# Wemos_P1_DSMR5_hat.net
KiCad netlist of a schematic drawn in EasyEDA
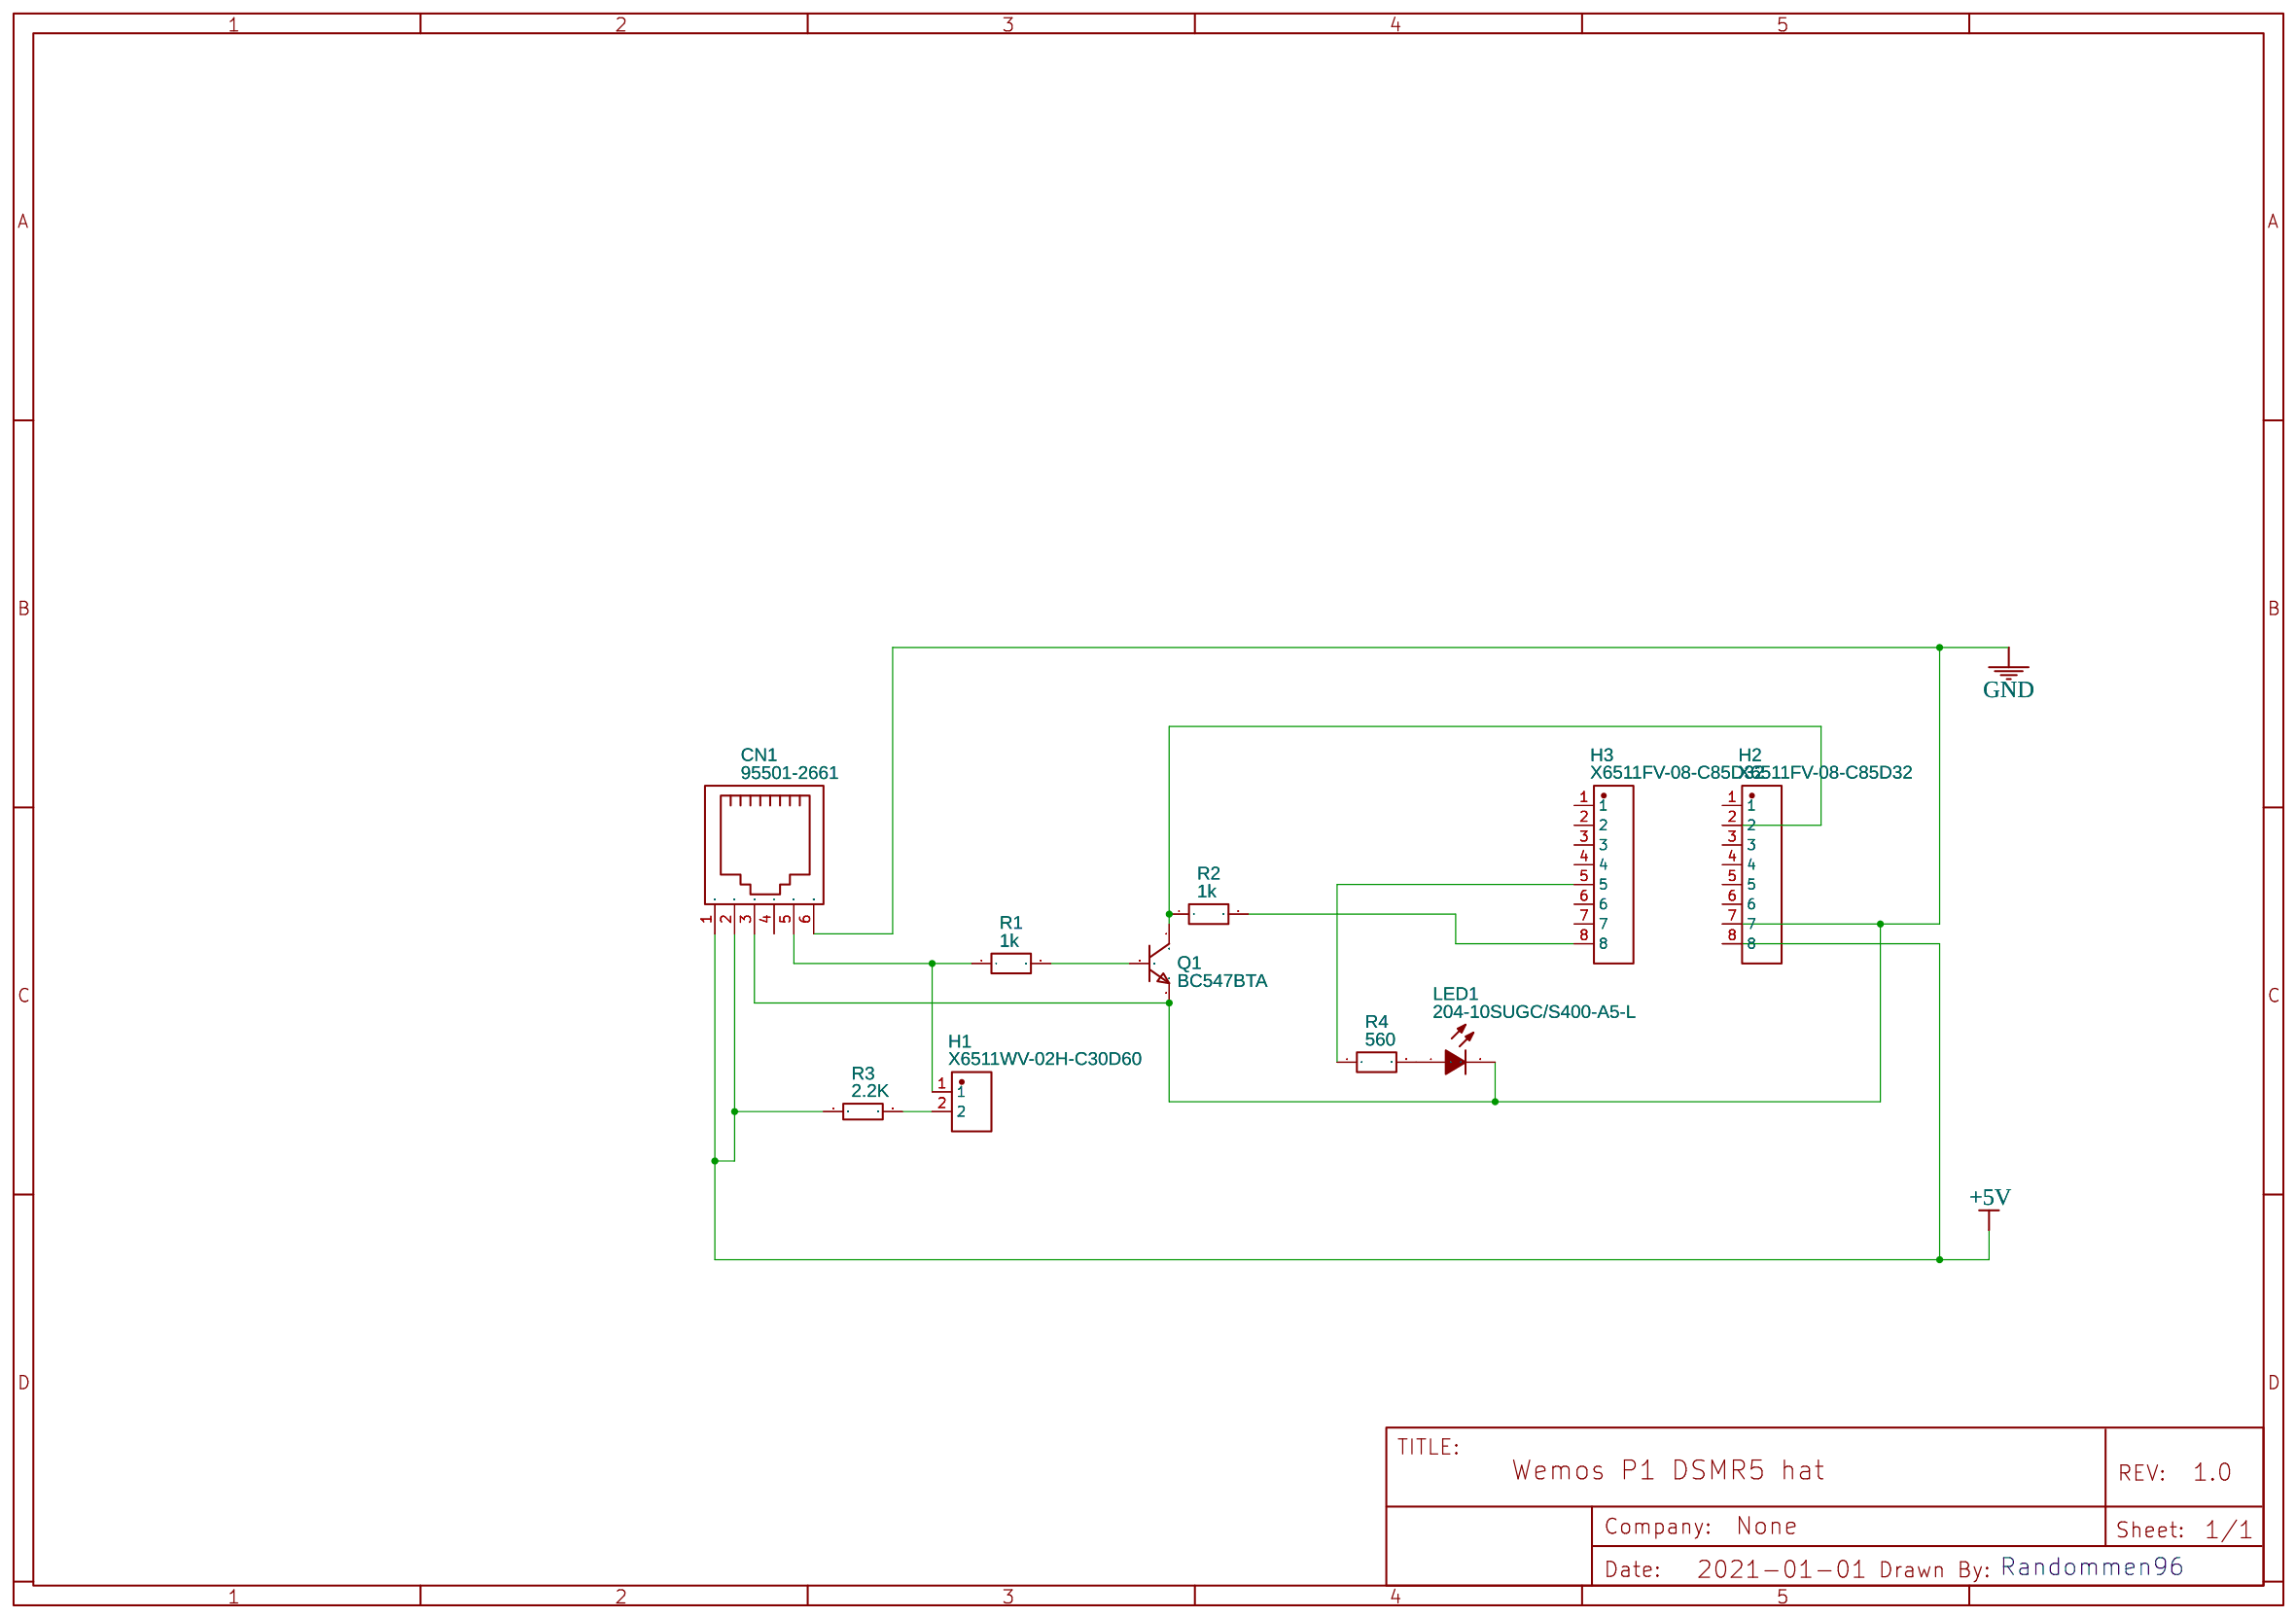
[diagram p0: schematic sheet]

(export (version "E")
  (design (tool "Eeschema 10.0.6"))
  (components
    (comp (ref "CN1")
      (value "95501-2661")
      (fields (field (name "BOM_Supplier Part") "C240856"))
      (libsource (lib "") (part "95501-2661"))
    )
    (comp (ref "H1")
      (value "X6511WV-02H-C30D60")
      (fields (field (name "BOM_Supplier Part") "C706874"))
      (libsource (lib "") (part "X6511WV-02H-C30D60"))
    )
    (comp (ref "H2")
      (value "X6511FV-08-C85D32")
      (fields (field (name "BOM_Supplier Part") "C718237"))
      (libsource (lib "") (part "X6511FV-08-C85D32"))
    )
    (comp (ref "H3")
      (value "X6511FV-08-C85D32")
      (fields (field (name "BOM_Supplier Part") "C718237"))
      (libsource (lib "") (part "X6511FV-08-C85D32"))
    )
    (comp (ref "LED1")
      (value "204-10SUGC/S400-A5-L")
      (fields (field (name "BOM_Supplier Part") "C99763"))
      (libsource (lib "") (part "204-10SUGC/S400-A5-L"))
    )
    (comp (ref "Q1")
      (value "BC547BTA")
      (fields (field (name "BOM_Supplier Part") "C258144"))
      (libsource (lib "") (part "BC547BTA"))
    )
    (comp (ref "R1")
      (value "1k")
      (fields
        (field (name "BOM_Manufacturer Part") "CFR0W4J0102A50")
        (field (name "BOM_Supplier Part") "C66649")
      )
      (libsource (lib "") (part "CFR0W4J0102A50_C66649"))
    )
    (comp (ref "R2")
      (value "1k")
      (fields
        (field (name "BOM_Manufacturer Part") "CFR0W4J0102A50")
        (field (name "BOM_Supplier Part") "C66649")
      )
      (libsource (lib "") (part "CFR0W4J0102A50_C66649"))
    )
    (comp (ref "R3")
      (value "2.2K")
      (fields
        (field (name "BOM_Manufacturer Part") "CFR0W4J0222A50")
        (field (name "BOM_Supplier Part") "C61295")
      )
      (libsource (lib "") (part "CFR0W4J0222A50"))
    )
    (comp (ref "R4")
      (value "560")
      (fields
        (field (name "BOM_Manufacturer Part") "RD 1/4W 560R J T/B A1")
        (field (name "BOM_Supplier Part") "C433706")
      )
      (libsource (lib "") (part "RD 1/4W 560R J T/B A1"))
    )
  )
  (nets
    (net (code "1") (name "+5V") (class "Default")
      (node (ref "CN1") (pin "1") (pinfunction "1_1") (pintype "unspecified"))
      (node (ref "CN1") (pin "2") (pinfunction "2_2") (pintype "unspecified"))
      (node (ref "H2") (pin "8") (pinfunction "8_8") (pintype "unspecified"))
      (node (ref "R3") (pin "1") (pinfunction "1_1") (pintype "input"))
    )
    (net (code "2") (name "GND") (class "Default")
      (node (ref "CN1") (pin "3") (pinfunction "3_3") (pintype "unspecified"))
      (node (ref "CN1") (pin "6") (pinfunction "6_6") (pintype "unspecified"))
      (node (ref "H2") (pin "7") (pinfunction "7_7") (pintype "unspecified"))
      (node (ref "LED1") (pin "2") (pinfunction "K_2") (pintype "input"))
      (node (ref "Q1") (pin "3") (pinfunction "E_3") (pintype "unspecified"))
    )
    (net (code "3") (name "Net-(CN1-Pad5)") (class "Default")
      (node (ref "CN1") (pin "5") (pinfunction "5_5") (pintype "unspecified"))
      (node (ref "H1") (pin "1") (pinfunction "1_1") (pintype "unspecified"))
      (node (ref "R1") (pin "1") (pinfunction "1_1") (pintype "unspecified"))
    )
    (net (code "4") (name "Net-(H1-Pad2)") (class "Default")
      (node (ref "H1") (pin "2") (pinfunction "2_2") (pintype "unspecified"))
      (node (ref "R3") (pin "2") (pinfunction "2_2") (pintype "input"))
    )
    (net (code "5") (name "Net-(H3-Pad5)") (class "Default")
      (node (ref "H3") (pin "5") (pinfunction "5_5") (pintype "unspecified"))
      (node (ref "R4") (pin "1") (pinfunction "1_1") (pintype "unspecified"))
    )
    (net (code "6") (name "Net-(H3-Pad8)") (class "Default")
      (node (ref "H3") (pin "8") (pinfunction "8_8") (pintype "unspecified"))
      (node (ref "R2") (pin "2") (pinfunction "2_2") (pintype "unspecified"))
    )
    (net (code "7") (name "Net-(LED1-A)") (class "Default")
      (node (ref "LED1") (pin "1") (pinfunction "A_1") (pintype "input"))
      (node (ref "R4") (pin "2") (pinfunction "2_2") (pintype "unspecified"))
    )
    (net (code "8") (name "Net-(Q1-B)") (class "Default")
      (node (ref "Q1") (pin "2") (pinfunction "B_2") (pintype "unspecified"))
      (node (ref "R1") (pin "2") (pinfunction "2_2") (pintype "unspecified"))
    )
    (net (code "9") (name "Net-(Q1-C)") (class "Default")
      (node (ref "H2") (pin "2") (pinfunction "2_2") (pintype "unspecified"))
      (node (ref "Q1") (pin "1") (pinfunction "C_1") (pintype "unspecified"))
      (node (ref "R2") (pin "1") (pinfunction "1_1") (pintype "unspecified"))
    )
    (net (code "10") (name "unconnected-(CN1-Pad4)") (class "Default")
      (node (ref "CN1") (pin "4") (pinfunction "4_4") (pintype "unspecified"))
    )
    (net (code "11") (name "unconnected-(H2-Pad1)") (class "Default")
      (node (ref "H2") (pin "1") (pinfunction "1_1") (pintype "unspecified"))
    )
    (net (code "12") (name "unconnected-(H2-Pad3)") (class "Default")
      (node (ref "H2") (pin "3") (pinfunction "3_3") (pintype "unspecified"))
    )
    (net (code "13") (name "unconnected-(H2-Pad4)") (class "Default")
      (node (ref "H2") (pin "4") (pinfunction "4_4") (pintype "unspecified"))
    )
    (net (code "14") (name "unconnected-(H2-Pad5)") (class "Default")
      (node (ref "H2") (pin "5") (pinfunction "5_5") (pintype "unspecified"))
    )
    (net (code "15") (name "unconnected-(H2-Pad6)") (class "Default")
      (node (ref "H2") (pin "6") (pinfunction "6_6") (pintype "unspecified"))
    )
    (net (code "16") (name "unconnected-(H3-Pad1)") (class "Default")
      (node (ref "H3") (pin "1") (pinfunction "1_1") (pintype "unspecified"))
    )
    (net (code "17") (name "unconnected-(H3-Pad2)") (class "Default")
      (node (ref "H3") (pin "2") (pinfunction "2_2") (pintype "unspecified"))
    )
    (net (code "18") (name "unconnected-(H3-Pad3)") (class "Default")
      (node (ref "H3") (pin "3") (pinfunction "3_3") (pintype "unspecified"))
    )
    (net (code "19") (name "unconnected-(H3-Pad4)") (class "Default")
      (node (ref "H3") (pin "4") (pinfunction "4_4") (pintype "unspecified"))
    )
    (net (code "20") (name "unconnected-(H3-Pad6)") (class "Default")
      (node (ref "H3") (pin "6") (pinfunction "6_6") (pintype "unspecified"))
    )
    (net (code "21") (name "unconnected-(H3-Pad7)") (class "Default")
      (node (ref "H3") (pin "7") (pinfunction "7_7") (pintype "unspecified"))
    )
  )
)
